# SIMCARD_SCH.net
KiCad netlist of a schematic drawn in Altium Designer
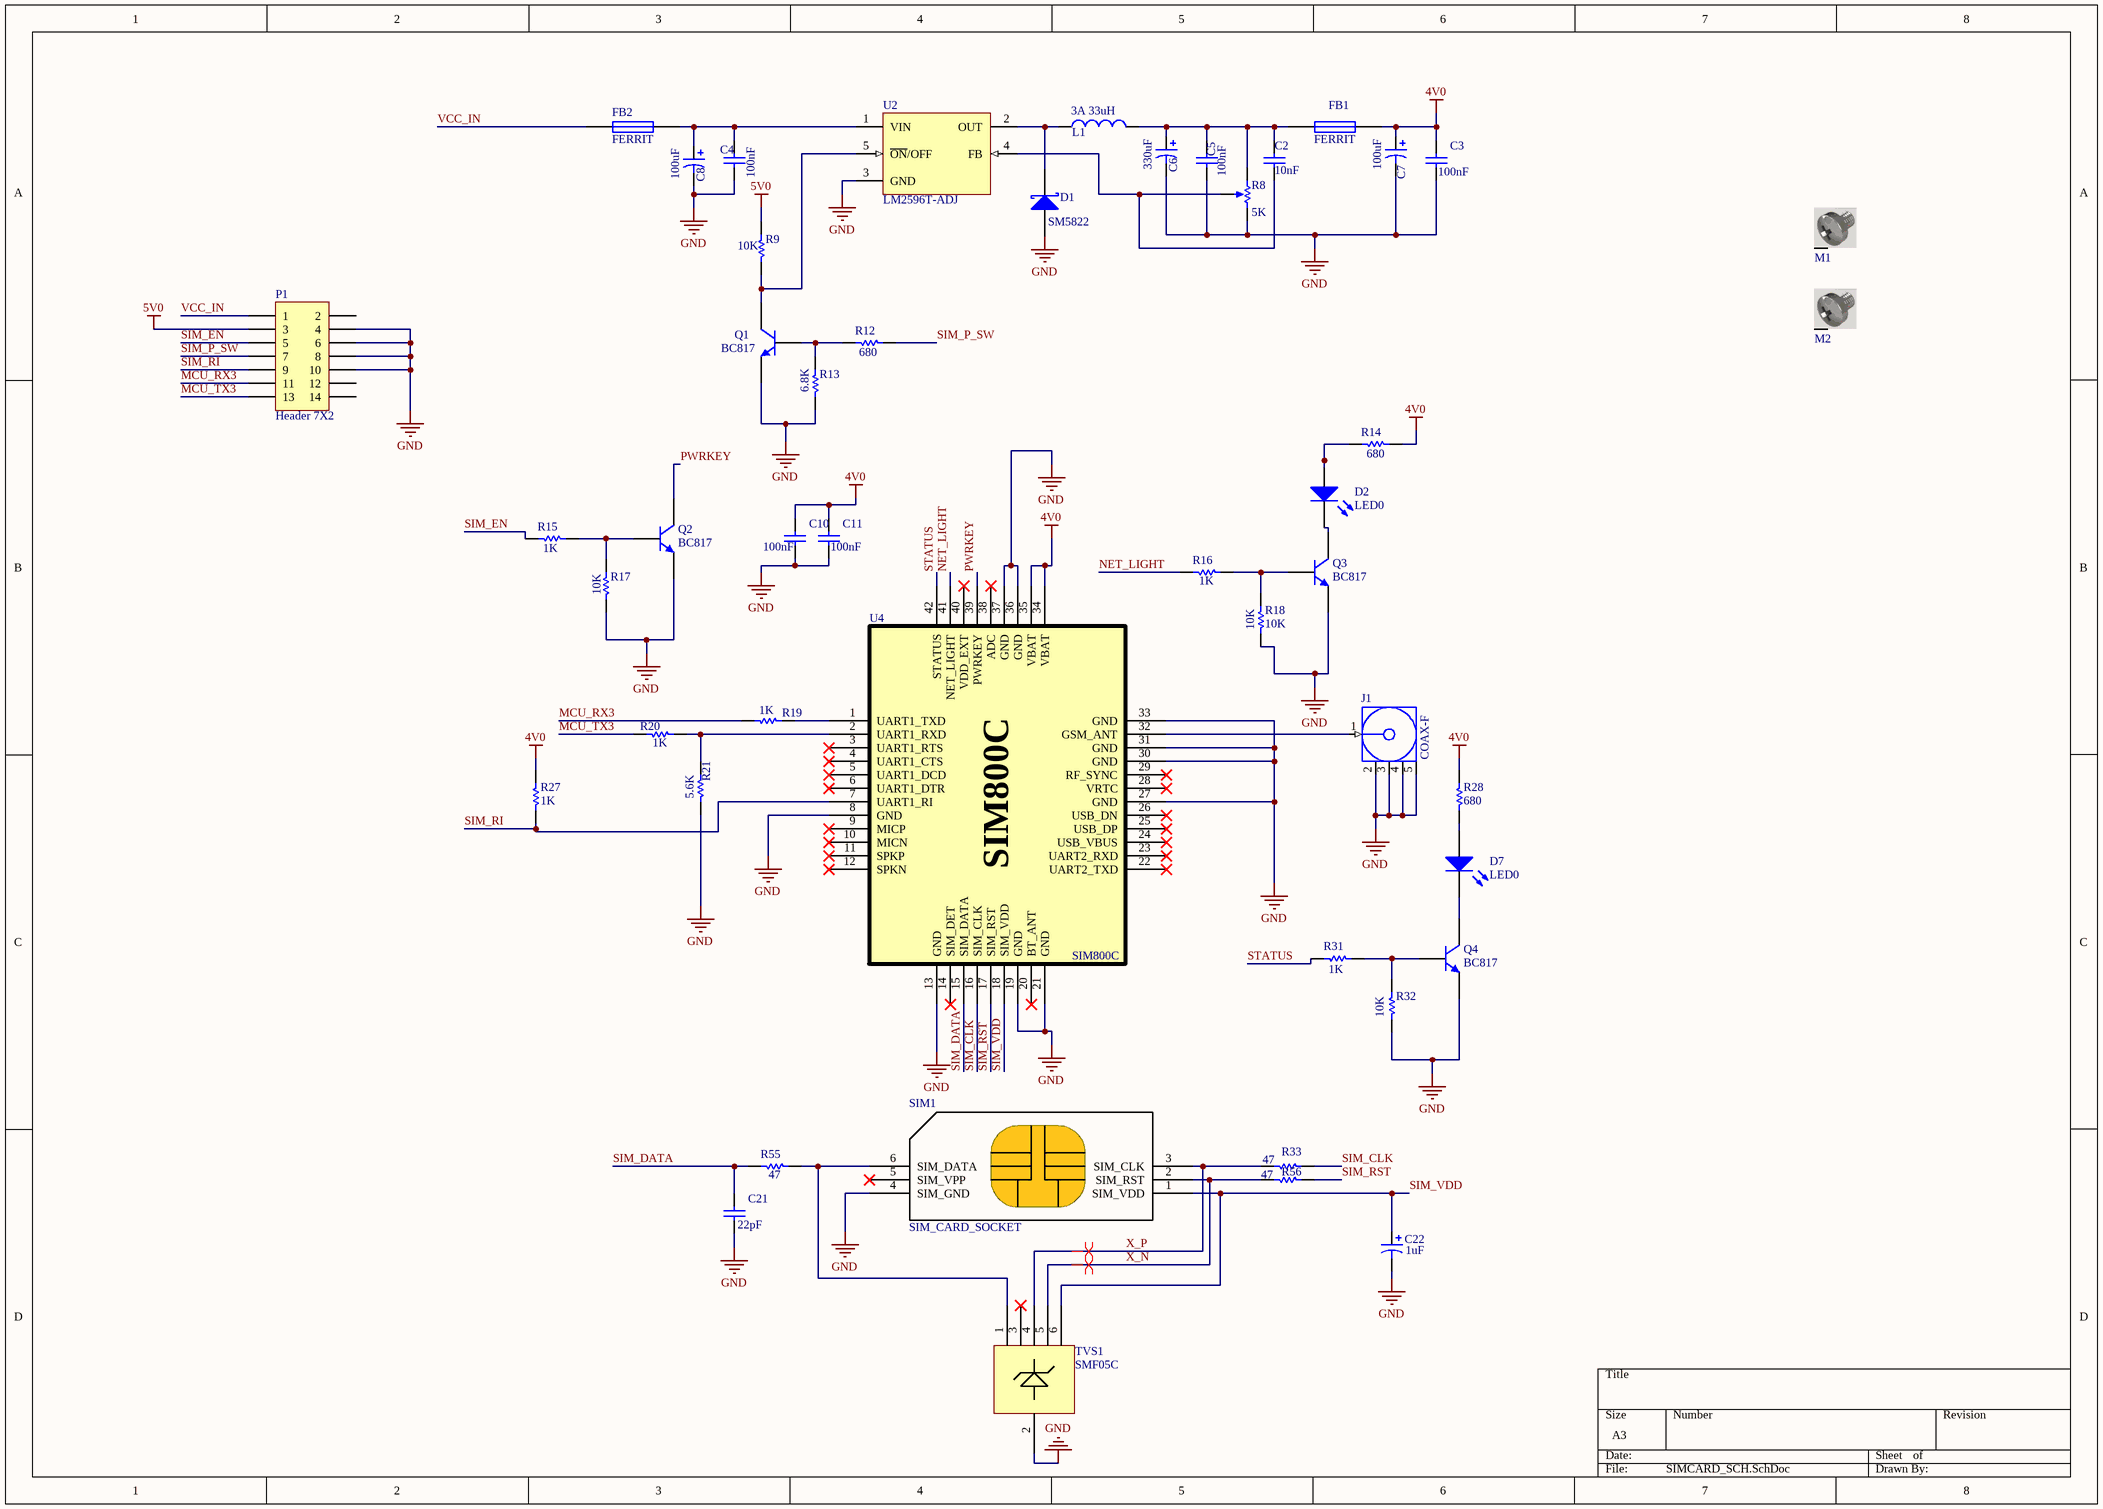
[diagram p0: SIMCARD_SCH.SchDoc]

(export (version "E")
  (design (tool "Eeschema 10.0.6"))
  (components
    (comp (ref "C2")
      (value "10nF")
      (footprint "SMD_805")
      (description "Capacitor")
      (fields (field (name "PUBLISHER") "Altium Limited"))
      (libsource (lib "Miscellaneous Devices") (part "Cap"))
    )
    (comp (ref "C3")
      (value "100nF")
      (footprint "SMD_805")
      (description "Capacitor")
      (fields (field (name "PUBLISHER") "Altium Limited"))
      (libsource (lib "Miscellaneous Devices") (part "Cap"))
    )
    (comp (ref "C4")
      (value "100nF")
      (footprint "SMD_805")
      (description "Capacitor")
      (fields (field (name "PUBLISHER") "Altium Limited"))
      (libsource (lib "Miscellaneous Devices") (part "Cap"))
    )
    (comp (ref "C5")
      (value "100nF")
      (footprint "SMD_805")
      (description "Capacitor")
      (fields (field (name "PUBLISHER") "Altium Limited"))
      (libsource (lib "Miscellaneous Devices") (part "Cap"))
    )
    (comp (ref "C6")
      (value "330uF")
      (footprint "C_CYL_SMD")
      (description "Polarized Capacitor (Radial)")
      (fields (field (name "PUBLISHER") "Altium Limited"))
      (libsource (lib "Miscellaneous Devices") (part "Cap Pol1"))
    )
    (comp (ref "C7")
      (value "100uF")
      (footprint "C_B")
      (description "Polarized Capacitor (Radial)")
      (fields (field (name "PUBLISHER") "Altium Limited"))
      (libsource (lib "Miscellaneous Devices") (part "Cap Pol1"))
    )
    (comp (ref "C8")
      (value "100uF")
      (footprint "C_B")
      (description "Polarized Capacitor (Radial)")
      (fields (field (name "PUBLISHER") "Altium Limited"))
      (libsource (lib "Miscellaneous Devices") (part "Cap Pol1"))
    )
    (comp (ref "C10")
      (value "100nF")
      (footprint "SMD_805")
      (description "Capacitor")
      (fields (field (name "PUBLISHER") "Altium Limited"))
      (libsource (lib "Miscellaneous Devices") (part "Cap"))
    )
    (comp (ref "C11")
      (value "100nF")
      (footprint "SMD_805")
      (description "Capacitor")
      (fields (field (name "PUBLISHER") "Altium Limited"))
      (libsource (lib "Miscellaneous Devices") (part "Cap"))
    )
    (comp (ref "C21")
      (value "22pF")
      (footprint "SMD_805")
      (description "Capacitor")
      (fields (field (name "PUBLISHER") "Altium Limited"))
      (libsource (lib "Miscellaneous Devices") (part "Cap"))
    )
    (comp (ref "C22")
      (value "1uF")
      (footprint "CAP_SMD_A")
      (description "Polarized Capacitor (Radial)")
      (fields (field (name "PUBLISHER") "Altium Limited"))
      (libsource (lib "Miscellaneous Devices") (part "Cap Pol1"))
    )
    (comp (ref "D1")
      (value "SM5822")
      (footprint "DO_214_AB_SMC")
      (description "Schottky Rectifier")
      (fields (field (name "PUBLISHER") "Altium Limited"))
      (libsource (lib "Miscellaneous Devices") (part "Diode 11DQ03"))
    )
    (comp (ref "D2")
      (value "LED0")
      (footprint "SMD_805")
      (description "Typical INFRARED GaAs LED")
      (fields (field (name "PUBLISHER") "Altium Limited"))
      (libsource (lib "Miscellaneous Devices") (part "LED0"))
    )
    (comp (ref "D7")
      (value "LED0")
      (footprint "SMD_805")
      (description "Typical INFRARED GaAs LED")
      (fields (field (name "PUBLISHER") "Altium Limited"))
      (libsource (lib "Miscellaneous Devices") (part "LED0"))
    )
    (comp (ref "FB1")
      (value "FERRIT")
      (footprint "smd_805")
      (description "Fuse")
      (fields (field (name "PUBLISHER") "Altium Limited"))
      (libsource (lib "Miscellaneous Devices") (part "Fuse 1"))
    )
    (comp (ref "FB2")
      (value "FERRIT")
      (footprint "smd_805")
      (description "Fuse")
      (fields (field (name "PUBLISHER") "Altium Limited"))
      (libsource (lib "Miscellaneous Devices") (part "Fuse 1"))
    )
    (comp (ref "J1")
      (value "COAX-F")
      (footprint "SMA")
      (fields (field (name "PUBLISHER") "Altium Limited"))
      (libsource (lib "Miscellaneous Connectors") (part "COAX-F"))
    )
    (comp (ref "L1")
      (value "33uH")
      (footprint "INDUC_SMD")
      (description "Inductor")
      (fields (field (name "CURRENT") "3A") (field (name "PUBLISHER") "Altium Limited"))
      (libsource (lib "Miscellaneous Devices") (part "Inductor"))
    )
    (comp (ref "M1")
      (value "Screw")
      (footprint "Board Screw_No Silk")
      (description "Board Screw With Spacer")
      (libsource (lib "NAHAL_LIB") (part "Board Screw"))
    )
    (comp (ref "M2")
      (value "Screw")
      (footprint "Board Screw_No Silk")
      (description "Board Screw With Spacer")
      (libsource (lib "NAHAL_LIB") (part "Board Screw"))
    )
    (comp (ref "P1")
      (value "Header 7X2")
      (footprint "HDR2X7")
      (description "Header, 7-Pin, Dual row")
      (fields (field (name "PUBLISHER") "Altium Limited"))
      (libsource (lib "Miscellaneous Connectors") (part "Header 7X2"))
    )
    (comp (ref "Q1")
      (value "BC817")
      (footprint "SOT23")
      (description "NPN Bipolar Transistor")
      (fields (field (name "PUBLISHER") "Altium Limited"))
      (libsource (lib "Miscellaneous Devices") (part "NPN"))
    )
    (comp (ref "Q2")
      (value "BC817")
      (footprint "SOT23")
      (description "NPN General Purpose Amplifier")
      (fields (field (name "PUBLISHER") "Altium Limited"))
      (libsource (lib "Miscellaneous Devices") (part "2N3904"))
    )
    (comp (ref "Q3")
      (value "BC817")
      (footprint "SOT23")
      (description "NPN General Purpose Amplifier")
      (fields (field (name "PUBLISHER") "Altium Limited"))
      (libsource (lib "Miscellaneous Devices") (part "2N3904"))
    )
    (comp (ref "Q4")
      (value "BC817")
      (footprint "SOT23")
      (description "NPN General Purpose Amplifier")
      (fields (field (name "PUBLISHER") "Altium Limited"))
      (libsource (lib "Miscellaneous Devices") (part "2N3904"))
    )
    (comp (ref "R8")
      (value "5K")
      (footprint "POT")
      (description "Potentiometer")
      (fields (field (name "Comment") "RPot") (field (name "PUBLISHER") "Altium Limited"))
      (libsource (lib "Miscellaneous Devices") (part "RPot"))
    )
    (comp (ref "R9")
      (value "10K")
      (footprint "SMD_805")
      (description "Resistor")
      (fields (field (name "PUBLISHER") "Altium Limited"))
      (libsource (lib "") (part "Res1_1"))
    )
    (comp (ref "R12")
      (value "680")
      (footprint "SMD_805")
      (description "Resistor")
      (fields (field (name "PUBLISHER") "Altium Limited"))
      (libsource (lib "") (part "Res1_1"))
    )
    (comp (ref "R13")
      (value "6.8K")
      (footprint "SMD_805")
      (description "Resistor")
      (fields (field (name "PUBLISHER") "Altium Limited"))
      (libsource (lib "Miscellaneous Devices") (part "Res1"))
    )
    (comp (ref "R14")
      (value "680")
      (footprint "SMD_805")
      (description "Resistor")
      (fields (field (name "PUBLISHER") "Altium Limited"))
      (libsource (lib "Miscellaneous Devices") (part "Res1"))
    )
    (comp (ref "R15")
      (value "1K")
      (footprint "SMD_805")
      (description "Resistor")
      (fields (field (name "PUBLISHER") "Altium Limited"))
      (libsource (lib "Miscellaneous Devices") (part "Res1"))
    )
    (comp (ref "R16")
      (value "1K")
      (footprint "SMD_805")
      (description "Resistor")
      (fields (field (name "PUBLISHER") "Altium Limited"))
      (libsource (lib "Miscellaneous Devices") (part "Res1"))
    )
    (comp (ref "R17")
      (value "10K")
      (footprint "SMD_805")
      (description "Resistor")
      (fields (field (name "PUBLISHER") "Altium Limited"))
      (libsource (lib "") (part "Res1_1"))
    )
    (comp (ref "R18")
      (value "10K")
      (footprint "SMD_805")
      (description "Resistor")
      (fields (field (name "ALTIUM_VALUE") "10K") (field (name "PUBLISHER") "Altium Limited"))
      (libsource (lib "") (part "Res1_1"))
    )
    (comp (ref "R19")
      (value "1K")
      (footprint "SMD_805")
      (description "Resistor")
      (fields (field (name "PUBLISHER") "Altium Limited"))
      (libsource (lib "Miscellaneous Devices") (part "Res1"))
    )
    (comp (ref "R20")
      (value "1K")
      (footprint "SMD_805")
      (description "Resistor")
      (fields (field (name "PUBLISHER") "Altium Limited"))
      (libsource (lib "Miscellaneous Devices") (part "Res1"))
    )
    (comp (ref "R21")
      (value "5.6K")
      (footprint "SMD_805")
      (description "Resistor")
      (fields (field (name "PUBLISHER") "Altium Limited"))
      (libsource (lib "") (part "Res1_1"))
    )
    (comp (ref "R27")
      (value "1K")
      (footprint "SMD_805")
      (description "Resistor")
      (fields (field (name "PUBLISHER") "Altium Limited"))
      (libsource (lib "") (part "Res1_1"))
    )
    (comp (ref "R28")
      (value "680")
      (footprint "SMD_805")
      (description "Resistor")
      (fields (field (name "PUBLISHER") "Altium Limited"))
      (libsource (lib "") (part "Res1_1"))
    )
    (comp (ref "R31")
      (value "1K")
      (footprint "SMD_805")
      (description "Resistor")
      (fields (field (name "PUBLISHER") "Altium Limited"))
      (libsource (lib "Miscellaneous Devices") (part "Res1"))
    )
    (comp (ref "R32")
      (value "10K")
      (footprint "SMD_805")
      (description "Resistor")
      (fields (field (name "PUBLISHER") "Altium Limited"))
      (libsource (lib "") (part "Res1_1"))
    )
    (comp (ref "R33")
      (value "47")
      (footprint "SMD_805")
      (description "Resistor")
      (fields (field (name "PUBLISHER") "Altium Limited"))
      (libsource (lib "Miscellaneous Devices") (part "Res1"))
    )
    (comp (ref "R55")
      (value "47")
      (footprint "SMD_805")
      (description "Resistor")
      (fields (field (name "PUBLISHER") "Altium Limited"))
      (libsource (lib "Miscellaneous Devices") (part "Res1"))
    )
    (comp (ref "R56")
      (value "47")
      (footprint "SMD_805")
      (description "Resistor")
      (fields (field (name "PUBLISHER") "Altium Limited"))
      (libsource (lib "Miscellaneous Devices") (part "Res1"))
    )
    (comp (ref "SIM1")
      (value "SIM_CARD_SOCKET")
      (footprint "SIM_CARD_HOLDER")
      (libsource (lib "SIM_CARD_SOCKET") (part "SIM_CARD_SOCKET"))
    )
    (comp (ref "TVS1")
      (value "SMF05C")
      (footprint "SMF05C_6L")
      (libsource (lib "TVS_ARRAY") (part "TVS_ARRAY"))
    )
    (comp (ref "U2")
      (value "LM2596T-ADJ")
      (footprint "LM2576_SMD")
      (description "SIMPLE SWITCHER Power Converter 150 KHz 3A Step-Down Voltage Regulator")
      (fields
        (field (name "MANUFACTURER") "National Semiconductor")
        (field (name "DIGIKEYPARTNUMBER") "LM2596T-ADJ-ND")
        (field (name "PUBLISHER") "Altium Limited")
      )
      (libsource (lib "NSC Switcher") (part "LM2596T-ADJ"))
    )
    (comp (ref "U4") (value "SIM800C") (footprint "SIM800C_3D") (libsource (lib "SIM800C") (part "SIM800C")))
  )
  (nets
    (net (code "1") (name "/MCU_RX3") (class "Default")
      (node (ref "P1") (pin "11") (pinfunction "11_11") (pintype "passive"))
      (node (ref "R19") (pin "2") (pinfunction "2_2") (pintype "passive"))
    )
    (net (code "2") (name "/MCU_TX3") (class "Default")
      (node (ref "P1") (pin "13") (pinfunction "13_13") (pintype "passive"))
      (node (ref "R20") (pin "2") (pinfunction "2_2") (pintype "passive"))
    )
    (net (code "3") (name "/NET_LIGHT") (class "Default")
      (node (ref "R16") (pin "1") (pinfunction "1_1") (pintype "passive"))
      (node (ref "U4") (pin "41") (pinfunction "NET_LIGHT_41") (pintype "passive"))
    )
    (net (code "4") (name "/PWRKEY") (class "Default")
      (node (ref "Q2") (pin "3") (pinfunction "C_3") (pintype "passive"))
      (node (ref "U4") (pin "39") (pinfunction "PWRKEY_39") (pintype "passive"))
    )
    (net (code "5") (name "/SIM_CLK") (class "Default")
      (node (ref "R33") (pin "2") (pinfunction "2_2") (pintype "passive"))
      (node (ref "U4") (pin "16") (pinfunction "SIM_CLK_16") (pintype "passive"))
    )
    (net (code "6") (name "/SIM_DATA") (class "Default")
      (node (ref "C21") (pin "2") (pinfunction "2_2") (pintype "passive"))
      (node (ref "R55") (pin "1") (pinfunction "1_1") (pintype "passive"))
      (node (ref "U4") (pin "15") (pinfunction "SIM_DATA_15") (pintype "passive"))
    )
    (net (code "7") (name "/SIM_EN") (class "Default")
      (node (ref "P1") (pin "5") (pinfunction "5_5") (pintype "passive"))
      (node (ref "R15") (pin "1") (pinfunction "1_1") (pintype "passive"))
    )
    (net (code "8") (name "/SIM_P_SW") (class "Default")
      (node (ref "P1") (pin "7") (pinfunction "7_7") (pintype "passive"))
      (node (ref "R12") (pin "2") (pinfunction "2_2") (pintype "passive"))
    )
    (net (code "9") (name "/SIM_RI") (class "Default")
      (node (ref "P1") (pin "9") (pinfunction "9_9") (pintype "passive"))
      (node (ref "R27") (pin "2") (pinfunction "2_2") (pintype "passive"))
      (node (ref "U4") (pin "7") (pinfunction "UART1_RI_7") (pintype "passive"))
    )
    (net (code "10") (name "/SIM_RST") (class "Default")
      (node (ref "R56") (pin "2") (pinfunction "2_2") (pintype "passive"))
      (node (ref "U4") (pin "17") (pinfunction "SIM_RST_17") (pintype "passive"))
    )
    (net (code "11") (name "/SIM_VDD") (class "Default")
      (node (ref "C22") (pin "1") (pinfunction "1_1") (pintype "passive"))
      (node (ref "SIM1") (pin "1") (pinfunction "SIM_VDD_1") (pintype "passive"))
      (node (ref "TVS1") (pin "6") (pintype "passive"))
      (node (ref "U4") (pin "18") (pinfunction "SIM_VDD_18") (pintype "passive"))
    )
    (net (code "12") (name "/STATUS") (class "Default")
      (node (ref "R31") (pin "1") (pinfunction "1_1") (pintype "passive"))
      (node (ref "U4") (pin "42") (pinfunction "STATUS_42") (pintype "passive"))
    )
    (net (code "13") (name "/VCC_IN") (class "Default")
      (node (ref "FB2") (pin "2") (pinfunction "2_2") (pintype "passive"))
      (node (ref "P1") (pin "1") (pinfunction "1_1") (pintype "passive"))
    )
    (net (code "14") (name "/X_N") (class "Default")
      (node (ref "R56") (pin "1") (pinfunction "1_1") (pintype "passive"))
      (node (ref "SIM1") (pin "2") (pinfunction "SIM_RST_2") (pintype "passive"))
      (node (ref "TVS1") (pin "5") (pintype "passive"))
    )
    (net (code "15") (name "/X_P") (class "Default")
      (node (ref "R33") (pin "1") (pinfunction "1_1") (pintype "passive"))
      (node (ref "SIM1") (pin "3") (pinfunction "SIM_CLK_3") (pintype "passive"))
      (node (ref "TVS1") (pin "4") (pintype "passive"))
    )
    (net (code "16") (name "4V0") (class "Default")
      (node (ref "C10") (pin "2") (pinfunction "2_2") (pintype "passive"))
      (node (ref "C11") (pin "2") (pinfunction "2_2") (pintype "passive"))
      (node (ref "C3") (pin "2") (pinfunction "2_2") (pintype "passive"))
      (node (ref "C7") (pin "1") (pinfunction "1_1") (pintype "passive"))
      (node (ref "FB1") (pin "2") (pinfunction "2_2") (pintype "passive"))
      (node (ref "R14") (pin "2") (pinfunction "2_2") (pintype "passive"))
      (node (ref "R27") (pin "1") (pinfunction "1_1") (pintype "passive"))
      (node (ref "R28") (pin "2") (pinfunction "2_2") (pintype "passive"))
      (node (ref "U4") (pin "34") (pinfunction "VBAT_34") (pintype "passive"))
      (node (ref "U4") (pin "35") (pinfunction "VBAT_35") (pintype "passive"))
    )
    (net (code "17") (name "5V0") (class "Default")
      (node (ref "P1") (pin "3") (pinfunction "3_3") (pintype "passive"))
      (node (ref "R9") (pin "2") (pinfunction "2_2") (pintype "passive"))
    )
    (net (code "18") (name "GND") (class "Default")
      (node (ref "C10") (pin "1") (pinfunction "1_1") (pintype "passive"))
      (node (ref "C11") (pin "1") (pinfunction "1_1") (pintype "passive"))
      (node (ref "C21") (pin "1") (pinfunction "1_1") (pintype "passive"))
      (node (ref "C22") (pin "2") (pinfunction "2_2") (pintype "passive"))
      (node (ref "C3") (pin "1") (pinfunction "1_1") (pintype "passive"))
      (node (ref "C4") (pin "1") (pinfunction "1_1") (pintype "passive"))
      (node (ref "C5") (pin "1") (pinfunction "1_1") (pintype "passive"))
      (node (ref "C6") (pin "2") (pinfunction "2_2") (pintype "passive"))
      (node (ref "C7") (pin "2") (pinfunction "2_2") (pintype "passive"))
      (node (ref "C8") (pin "2") (pinfunction "2_2") (pintype "passive"))
      (node (ref "D1") (pin "1") (pinfunction "A_1") (pintype "passive"))
      (node (ref "J1") (pin "2") (pinfunction "GND_2") (pintype "power_in"))
      (node (ref "J1") (pin "3") (pinfunction "GND_3") (pintype "power_in"))
      (node (ref "J1") (pin "4") (pinfunction "GND_4") (pintype "power_in"))
      (node (ref "J1") (pin "5") (pinfunction "GND_5") (pintype "power_in"))
      (node (ref "P1") (pin "10") (pinfunction "10_10") (pintype "passive"))
      (node (ref "P1") (pin "4") (pinfunction "4_4") (pintype "passive"))
      (node (ref "P1") (pin "6") (pinfunction "6_6") (pintype "passive"))
      (node (ref "P1") (pin "8") (pinfunction "8_8") (pintype "passive"))
      (node (ref "Q1") (pin "2") (pinfunction "E_2") (pintype "passive"))
      (node (ref "Q2") (pin "2") (pinfunction "E_2") (pintype "passive"))
      (node (ref "Q3") (pin "2") (pinfunction "E_2") (pintype "passive"))
      (node (ref "Q4") (pin "2") (pinfunction "E_2") (pintype "passive"))
      (node (ref "R13") (pin "1") (pinfunction "1_1") (pintype "passive"))
      (node (ref "R17") (pin "2") (pinfunction "2_2") (pintype "passive"))
      (node (ref "R18") (pin "2") (pinfunction "2_2") (pintype "passive"))
      (node (ref "R21") (pin "1") (pinfunction "1_1") (pintype "passive"))
      (node (ref "R32") (pin "2") (pinfunction "2_2") (pintype "passive"))
      (node (ref "R8") (pin "2") (pinfunction "BOT_2") (pintype "passive"))
      (node (ref "SIM1") (pin "4") (pinfunction "SIM_GND_4") (pintype "passive"))
      (node (ref "TVS1") (pin "2") (pintype "passive"))
      (node (ref "U2") (pin "3") (pinfunction "GND_3") (pintype "power_in"))
      (node (ref "U4") (pin "13") (pinfunction "GND_13") (pintype "passive"))
      (node (ref "U4") (pin "19") (pinfunction "GND_19") (pintype "passive"))
      (node (ref "U4") (pin "21") (pinfunction "GND_21") (pintype "passive"))
      (node (ref "U4") (pin "27") (pinfunction "GND_27") (pintype "passive"))
      (node (ref "U4") (pin "30") (pinfunction "GND_30") (pintype "passive"))
      (node (ref "U4") (pin "31") (pinfunction "GND_31") (pintype "passive"))
      (node (ref "U4") (pin "33") (pinfunction "GND_33") (pintype "passive"))
      (node (ref "U4") (pin "36") (pinfunction "GND_36") (pintype "passive"))
      (node (ref "U4") (pin "37") (pinfunction "GND_37") (pintype "passive"))
      (node (ref "U4") (pin "8") (pinfunction "GND_8") (pintype "passive"))
    )
    (net (code "19") (name "Net-(D1-K)") (class "Default")
      (node (ref "D1") (pin "2") (pinfunction "K_2") (pintype "passive"))
      (node (ref "L1") (pin "1") (pinfunction "1_1") (pintype "passive"))
      (node (ref "U2") (pin "2") (pinfunction "OUT_2") (pintype "power_in"))
    )
    (net (code "20") (name "Net-(D2-A)") (class "Default")
      (node (ref "D2") (pin "1") (pinfunction "A_1") (pintype "passive"))
      (node (ref "R14") (pin "1") (pinfunction "1_1") (pintype "passive"))
    )
    (net (code "21") (name "Net-(D2-K)") (class "Default")
      (node (ref "D2") (pin "2") (pinfunction "K_2") (pintype "passive"))
      (node (ref "Q3") (pin "3") (pinfunction "C_3") (pintype "passive"))
    )
    (net (code "22") (name "Net-(D7-A)") (class "Default")
      (node (ref "D7") (pin "1") (pinfunction "A_1") (pintype "passive"))
      (node (ref "R28") (pin "1") (pinfunction "1_1") (pintype "passive"))
    )
    (net (code "23") (name "Net-(D7-K)") (class "Default")
      (node (ref "D7") (pin "2") (pinfunction "K_2") (pintype "passive"))
      (node (ref "Q4") (pin "3") (pinfunction "C_3") (pintype "passive"))
    )
    (net (code "24") (name "Net-(J1-Signal)") (class "Default")
      (node (ref "J1") (pin "1") (pinfunction "Signal_1") (pintype "input"))
      (node (ref "U4") (pin "32") (pinfunction "GSM_ANT_32") (pintype "passive"))
    )
    (net (code "25") (name "Net-(Q1-B)") (class "Default")
      (node (ref "Q1") (pin "1") (pinfunction "B_1") (pintype "passive"))
      (node (ref "R12") (pin "1") (pinfunction "1_1") (pintype "passive"))
      (node (ref "R13") (pin "2") (pinfunction "2_2") (pintype "passive"))
    )
    (net (code "26") (name "Net-(Q1-C)") (class "Default")
      (node (ref "Q1") (pin "3") (pinfunction "C_3") (pintype "passive"))
      (node (ref "R9") (pin "1") (pinfunction "1_1") (pintype "passive"))
      (node (ref "U2") (pin "5") (pinfunction "~{ON}/OFF_5") (pintype "input"))
    )
    (net (code "27") (name "Net-(Q2-B)") (class "Default")
      (node (ref "Q2") (pin "1") (pinfunction "B_1") (pintype "passive"))
      (node (ref "R15") (pin "2") (pinfunction "2_2") (pintype "passive"))
      (node (ref "R17") (pin "1") (pinfunction "1_1") (pintype "passive"))
    )
    (net (code "28") (name "Net-(Q3-B)") (class "Default")
      (node (ref "Q3") (pin "1") (pinfunction "B_1") (pintype "passive"))
      (node (ref "R16") (pin "2") (pinfunction "2_2") (pintype "passive"))
      (node (ref "R18") (pin "1") (pinfunction "1_1") (pintype "passive"))
    )
    (net (code "29") (name "Net-(Q4-B)") (class "Default")
      (node (ref "Q4") (pin "1") (pinfunction "B_1") (pintype "passive"))
      (node (ref "R31") (pin "2") (pinfunction "2_2") (pintype "passive"))
      (node (ref "R32") (pin "1") (pinfunction "1_1") (pintype "passive"))
    )
    (net (code "30") (name "Net-(R8-TAP)") (class "Default")
      (node (ref "C2") (pin "1") (pinfunction "1_1") (pintype "passive"))
      (node (ref "R8") (pin "3") (pinfunction "TAP_3") (pintype "passive"))
      (node (ref "U2") (pin "4") (pinfunction "FB_4") (pintype "input"))
    )
    (net (code "31") (name "Net-(R8-TOP)") (class "Default")
      (node (ref "C2") (pin "2") (pinfunction "2_2") (pintype "passive"))
      (node (ref "C5") (pin "2") (pinfunction "2_2") (pintype "passive"))
      (node (ref "C6") (pin "1") (pinfunction "1_1") (pintype "passive"))
      (node (ref "FB1") (pin "1") (pinfunction "1_1") (pintype "passive"))
      (node (ref "L1") (pin "2") (pinfunction "2_2") (pintype "passive"))
      (node (ref "R8") (pin "1") (pinfunction "TOP_1") (pintype "passive"))
    )
    (net (code "32") (name "Net-(SIM1-SIM_DATA)") (class "Default")
      (node (ref "R55") (pin "2") (pinfunction "2_2") (pintype "passive"))
      (node (ref "SIM1") (pin "6") (pinfunction "SIM_DATA_6") (pintype "passive"))
      (node (ref "TVS1") (pin "1") (pintype "passive"))
    )
    (net (code "33") (name "Net-(U2-VIN)") (class "Default")
      (node (ref "C4") (pin "2") (pinfunction "2_2") (pintype "passive"))
      (node (ref "C8") (pin "1") (pinfunction "1_1") (pintype "passive"))
      (node (ref "FB2") (pin "1") (pinfunction "1_1") (pintype "passive"))
      (node (ref "U2") (pin "1") (pinfunction "VIN_1") (pintype "power_in"))
    )
    (net (code "34") (name "Net-(U4-UART1_RXD)") (class "Default")
      (node (ref "R20") (pin "1") (pinfunction "1_1") (pintype "passive"))
      (node (ref "R21") (pin "2") (pinfunction "2_2") (pintype "passive"))
      (node (ref "U4") (pin "2") (pinfunction "UART1_RXD_2") (pintype "passive"))
    )
    (net (code "35") (name "Net-(U4-UART1_TXD)") (class "Default")
      (node (ref "R19") (pin "1") (pinfunction "1_1") (pintype "passive"))
      (node (ref "U4") (pin "1") (pinfunction "UART1_TXD_1") (pintype "passive"))
    )
    (net (code "36") (name "unconnected-(M1-PadS)") (class "Default")
      (node (ref "M1") (pin "S") (pinfunction "S_S") (pintype "passive"))
    )
    (net (code "37") (name "unconnected-(M2-PadS)") (class "Default")
      (node (ref "M2") (pin "S") (pinfunction "S_S") (pintype "passive"))
    )
    (net (code "38") (name "unconnected-(P1-Pad2)") (class "Default")
      (node (ref "P1") (pin "2") (pinfunction "2_2") (pintype "passive"))
    )
    (net (code "39") (name "unconnected-(P1-Pad12)") (class "Default")
      (node (ref "P1") (pin "12") (pinfunction "12_12") (pintype "passive"))
    )
    (net (code "40") (name "unconnected-(P1-Pad14)") (class "Default")
      (node (ref "P1") (pin "14") (pinfunction "14_14") (pintype "passive"))
    )
    (net (code "41") (name "unconnected-(SIM1-SIM_VPP-Pad5)") (class "Default")
      (node (ref "SIM1") (pin "5") (pinfunction "SIM_VPP_5") (pintype "passive+no_connect"))
    )
    (net (code "42") (name "unconnected-(TVS1-Pad3)") (class "Default")
      (node (ref "TVS1") (pin "3") (pintype "passive+no_connect"))
    )
    (net (code "43") (name "unconnected-(U4-ADC-Pad38)") (class "Default")
      (node (ref "U4") (pin "38") (pinfunction "ADC_38") (pintype "passive+no_connect"))
    )
    (net (code "44") (name "unconnected-(U4-BT_ANT-Pad20)") (class "Default")
      (node (ref "U4") (pin "20") (pinfunction "BT_ANT_20") (pintype "passive+no_connect"))
    )
    (net (code "45") (name "unconnected-(U4-MICN-Pad10)") (class "Default")
      (node (ref "U4") (pin "10") (pinfunction "MICN_10") (pintype "passive+no_connect"))
    )
    (net (code "46") (name "unconnected-(U4-MICP-Pad9)") (class "Default")
      (node (ref "U4") (pin "9") (pinfunction "MICP_9") (pintype "passive+no_connect"))
    )
    (net (code "47") (name "unconnected-(U4-RF_SYNC-Pad29)") (class "Default")
      (node (ref "U4") (pin "29") (pinfunction "RF_SYNC_29") (pintype "passive+no_connect"))
    )
    (net (code "48") (name "unconnected-(U4-SIM_DET-Pad14)") (class "Default")
      (node (ref "U4") (pin "14") (pinfunction "SIM_DET_14") (pintype "passive+no_connect"))
    )
    (net (code "49") (name "unconnected-(U4-SPKN-Pad12)") (class "Default")
      (node (ref "U4") (pin "12") (pinfunction "SPKN_12") (pintype "passive+no_connect"))
    )
    (net (code "50") (name "unconnected-(U4-SPKP-Pad11)") (class "Default")
      (node (ref "U4") (pin "11") (pinfunction "SPKP_11") (pintype "passive+no_connect"))
    )
    (net (code "51") (name "unconnected-(U4-UART1_CTS-Pad4)") (class "Default")
      (node (ref "U4") (pin "4") (pinfunction "UART1_CTS_4") (pintype "passive+no_connect"))
    )
    (net (code "52") (name "unconnected-(U4-UART1_DCD-Pad5)") (class "Default")
      (node (ref "U4") (pin "5") (pinfunction "UART1_DCD_5") (pintype "passive+no_connect"))
    )
    (net (code "53") (name "unconnected-(U4-UART1_DTR-Pad6)") (class "Default")
      (node (ref "U4") (pin "6") (pinfunction "UART1_DTR_6") (pintype "passive+no_connect"))
    )
    (net (code "54") (name "unconnected-(U4-UART1_RTS-Pad3)") (class "Default")
      (node (ref "U4") (pin "3") (pinfunction "UART1_RTS_3") (pintype "passive+no_connect"))
    )
    (net (code "55") (name "unconnected-(U4-UART2_RXD-Pad23)") (class "Default")
      (node (ref "U4") (pin "23") (pinfunction "UART2_RXD_23") (pintype "passive+no_connect"))
    )
    (net (code "56") (name "unconnected-(U4-UART2_TXD-Pad22)") (class "Default")
      (node (ref "U4") (pin "22") (pinfunction "UART2_TXD_22") (pintype "passive+no_connect"))
    )
    (net (code "57") (name "unconnected-(U4-USB_DN-Pad26)") (class "Default")
      (node (ref "U4") (pin "26") (pinfunction "USB_DN_26") (pintype "passive+no_connect"))
    )
    (net (code "58") (name "unconnected-(U4-USB_DP-Pad25)") (class "Default")
      (node (ref "U4") (pin "25") (pinfunction "USB_DP_25") (pintype "passive+no_connect"))
    )
    (net (code "59") (name "unconnected-(U4-USB_VBUS-Pad24)") (class "Default")
      (node (ref "U4") (pin "24") (pinfunction "USB_VBUS_24") (pintype "passive+no_connect"))
    )
    (net (code "60") (name "unconnected-(U4-VDD_EXT-Pad40)") (class "Default")
      (node (ref "U4") (pin "40") (pinfunction "VDD_EXT_40") (pintype "passive+no_connect"))
    )
    (net (code "61") (name "unconnected-(U4-VRTC-Pad28)") (class "Default")
      (node (ref "U4") (pin "28") (pinfunction "VRTC_28") (pintype "passive+no_connect"))
    )
  )
)
